# SmartCard.net
KiCad netlist of a schematic drawn in Altium Designer
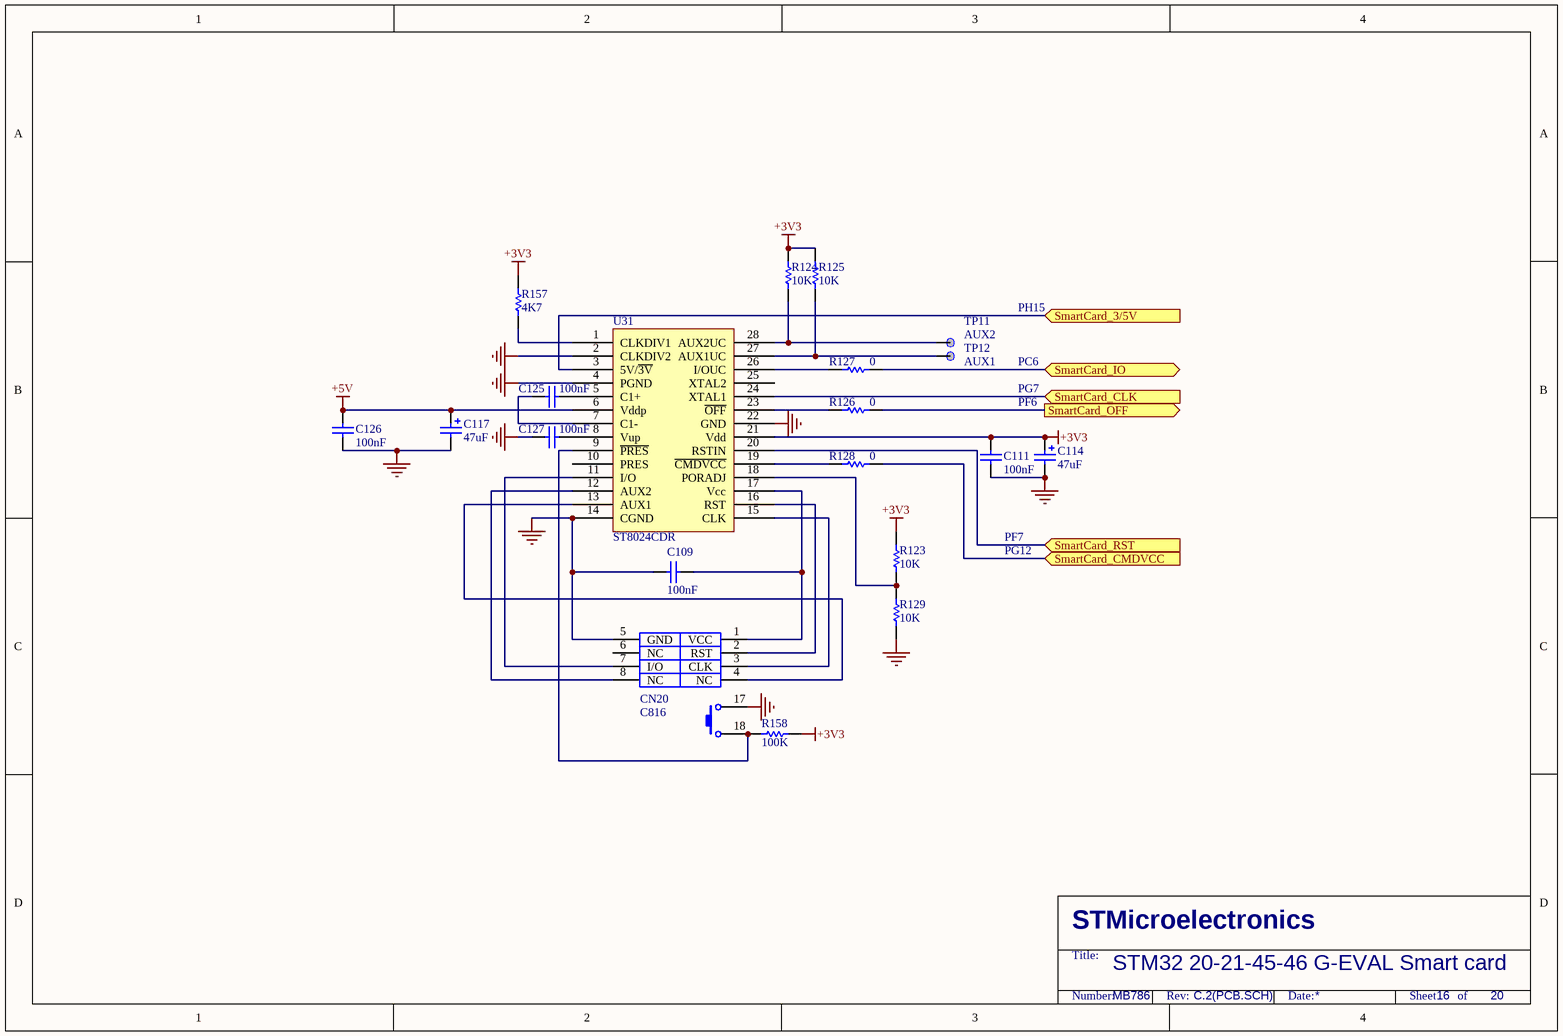
[diagram p0: SmartCard.SchDoc]

(export (version "E")
  (design (tool "Eeschema 10.0.6"))
  (components
    (comp (ref "C109")
      (value "100nF")
      (footprint "0402C")
      (description "Capacitor")
      (fields (field (name "PUBLISHER") "Altium Limited"))
      (libsource (lib "Miscellaneous Devices") (part "CAP"))
    )
    (comp (ref "C111")
      (value "100nF")
      (footprint "0402C")
      (description "Capacitor")
      (fields (field (name "PUBLISHER") "Altium Limited"))
      (libsource (lib "Miscellaneous Devices") (part "CAP"))
    )
    (comp (ref "C114")
      (value "47uF")
      (footprint "TAN-B")
      (description "Polarized Capacitor (Radial)")
      (fields (field (name "PUBLISHER") "Altium Limited"))
      (libsource (lib "Miscellaneous Devices") (part "Cap Pol1"))
    )
    (comp (ref "C117")
      (value "47uF")
      (footprint "TAN-B")
      (description "Polarized Capacitor (Radial)")
      (fields (field (name "PUBLISHER") "Altium Limited"))
      (libsource (lib "Miscellaneous Devices") (part "Cap Pol1"))
    )
    (comp (ref "C125")
      (value "100nF")
      (footprint "0402C")
      (description "Capacitor")
      (fields (field (name "PUBLISHER") "Altium Limited"))
      (libsource (lib "Miscellaneous Devices") (part "CAP"))
    )
    (comp (ref "C126")
      (value "100nF")
      (footprint "0402C")
      (description "Capacitor")
      (fields (field (name "PUBLISHER") "Altium Limited"))
      (libsource (lib "Miscellaneous Devices") (part "CAP"))
    )
    (comp (ref "C127")
      (value "100nF")
      (footprint "0402C")
      (description "Capacitor")
      (fields (field (name "PUBLISHER") "Altium Limited"))
      (libsource (lib "Miscellaneous Devices") (part "CAP"))
    )
    (comp (ref "CN20")
      (value "C816")
      (footprint "SAM(C816)")
      (libsource (lib "MB525") (part "Smart_card_CN"))
    )
    (comp (ref "R123")
      (value "10K")
      (footprint "0402R")
      (description "Resistor")
      (fields (field (name "PUBLISHER") "Altium Limited"))
      (libsource (lib "Miscellaneous Devices") (part "Res1"))
    )
    (comp (ref "R124")
      (value "10K")
      (footprint "0402R")
      (description "Resistor")
      (fields (field (name "PUBLISHER") "Altium Limited"))
      (libsource (lib "Miscellaneous Devices") (part "Res1"))
    )
    (comp (ref "R125")
      (value "10K")
      (footprint "0402R")
      (description "Resistor")
      (fields (field (name "PUBLISHER") "Altium Limited"))
      (libsource (lib "Miscellaneous Devices") (part "Res1"))
    )
    (comp (ref "R126")
      (value "0")
      (footprint "0603R")
      (description "Resistor")
      (fields (field (name "PUBLISHER") "Altium Limited"))
      (libsource (lib "Miscellaneous Devices") (part "Res1"))
    )
    (comp (ref "R127")
      (value "0")
      (footprint "0603R")
      (description "Resistor")
      (fields (field (name "PUBLISHER") "Altium Limited"))
      (libsource (lib "Miscellaneous Devices") (part "Res1"))
    )
    (comp (ref "R128")
      (value "0")
      (footprint "0603R")
      (description "Resistor")
      (fields (field (name "PUBLISHER") "Altium Limited"))
      (libsource (lib "Miscellaneous Devices") (part "Res1"))
    )
    (comp (ref "R129")
      (value "10K")
      (footprint "0402R")
      (description "Resistor")
      (fields (field (name "PUBLISHER") "Altium Limited"))
      (libsource (lib "Miscellaneous Devices") (part "Res1"))
    )
    (comp (ref "R157")
      (value "4K7")
      (footprint "0402R")
      (description "Resistor")
      (fields (field (name "PUBLISHER") "Altium Limited"))
      (libsource (lib "Miscellaneous Devices") (part "Res1"))
    )
    (comp (ref "R158")
      (value "100K")
      (footprint "0402R")
      (description "Resistor")
      (fields (field (name "PUBLISHER") "Altium Limited"))
      (libsource (lib "Miscellaneous Devices") (part "Res1"))
    )
    (comp (ref "TP11") (value "AUX2") (footprint "TP") (libsource (lib "*") (part "TP")))
    (comp (ref "TP12") (value "AUX1") (footprint "TP") (libsource (lib "*") (part "TP")))
    (comp (ref "U31") (value "ST8024CDR") (footprint "SO28") (libsource (lib "MB525") (part "ST8024CTR")))
  )
  (nets
    (net (code "1") (name "+3V3") (class "Default")
      (node (ref "C111") (pin "1") (pinfunction "1_1") (pintype "passive"))
      (node (ref "C114") (pin "1") (pinfunction "1_1") (pintype "passive"))
      (node (ref "R123") (pin "1") (pinfunction "1_1") (pintype "passive"))
      (node (ref "R124") (pin "1") (pinfunction "1_1") (pintype "passive"))
      (node (ref "R125") (pin "1") (pinfunction "1_1") (pintype "passive"))
      (node (ref "R157") (pin "1") (pinfunction "1_1") (pintype "passive"))
      (node (ref "R158") (pin "1") (pinfunction "1_1") (pintype "passive"))
      (node (ref "U31") (pin "21") (pinfunction "Vdd_21") (pintype "passive"))
    )
    (net (code "2") (name "+5V") (class "Default")
      (node (ref "C117") (pin "1") (pinfunction "1_1") (pintype "passive"))
      (node (ref "C126") (pin "1") (pinfunction "1_1") (pintype "passive"))
      (node (ref "U31") (pin "6") (pinfunction "Vddp_6") (pintype "passive"))
    )
    (net (code "3") (name "/SmartCard_3{slash}5V") (class "Default")
      (node (ref "U31") (pin "3") (pinfunction "5V/~{3V}_3") (pintype "passive"))
    )
    (net (code "4") (name "/SmartCard_CLK") (class "Default")
      (node (ref "U31") (pin "24") (pinfunction "XTAL1_24") (pintype "passive"))
    )
    (net (code "5") (name "/SmartCard_CMDVCC") (class "Default")
      (node (ref "R128") (pin "1") (pinfunction "1_1") (pintype "passive"))
    )
    (net (code "6") (name "/SmartCard_IO") (class "Default")
      (node (ref "R127") (pin "2") (pinfunction "2_2") (pintype "passive"))
    )
    (net (code "7") (name "/SmartCard_OFF") (class "Default")
      (node (ref "R126") (pin "1") (pinfunction "1_1") (pintype "passive"))
    )
    (net (code "8") (name "/SmartCard_RST") (class "Default")
      (node (ref "U31") (pin "20") (pinfunction "RSTIN_20") (pintype "passive"))
    )
    (net (code "9") (name "GND") (class "Default")
      (node (ref "C109") (pin "1") (pinfunction "1_1") (pintype "passive"))
      (node (ref "C111") (pin "2") (pinfunction "2_2") (pintype "passive"))
      (node (ref "C114") (pin "2") (pinfunction "2_2") (pintype "passive"))
      (node (ref "C117") (pin "2") (pinfunction "2_2") (pintype "passive"))
      (node (ref "C126") (pin "2") (pinfunction "2_2") (pintype "passive"))
      (node (ref "C127") (pin "2") (pinfunction "2_2") (pintype "passive"))
      (node (ref "CN20") (pin "17") (pintype "passive"))
      (node (ref "CN20") (pin "5") (pinfunction "GND_5") (pintype "passive"))
      (node (ref "R129") (pin "2") (pinfunction "2_2") (pintype "passive"))
      (node (ref "U31") (pin "14") (pinfunction "CGND_14") (pintype "passive"))
      (node (ref "U31") (pin "2") (pinfunction "CLKDIV2_2") (pintype "passive"))
      (node (ref "U31") (pin "22") (pinfunction "GND_22") (pintype "passive"))
      (node (ref "U31") (pin "4") (pinfunction "PGND_4") (pintype "passive"))
    )
    (net (code "10") (name "Net-(CN20-CLK)") (class "Default")
      (node (ref "CN20") (pin "3") (pinfunction "CLK_3") (pintype "passive"))
      (node (ref "U31") (pin "15") (pinfunction "CLK_15") (pintype "passive"))
    )
    (net (code "11") (name "Net-(CN20-I{slash}O)") (class "Default")
      (node (ref "CN20") (pin "7") (pinfunction "I/O_7") (pintype "passive"))
      (node (ref "U31") (pin "11") (pinfunction "I/O_11") (pintype "passive"))
    )
    (net (code "12") (name "Net-(CN20-RST)") (class "Default")
      (node (ref "CN20") (pin "2") (pinfunction "RST_2") (pintype "passive"))
      (node (ref "U31") (pin "16") (pinfunction "RST_16") (pintype "passive"))
    )
    (net (code "13") (name "Net-(CN20-VCC)") (class "Default")
      (node (ref "C109") (pin "2") (pinfunction "2_2") (pintype "passive"))
      (node (ref "CN20") (pin "1") (pinfunction "VCC_1") (pintype "passive"))
      (node (ref "U31") (pin "17") (pinfunction "Vcc_17") (pintype "passive"))
    )
    (net (code "14") (name "Net-(U31-AUX1)") (class "Default")
      (node (ref "CN20") (pin "4") (pinfunction "NC_4") (pintype "passive"))
      (node (ref "U31") (pin "13") (pinfunction "AUX1_13") (pintype "passive"))
    )
    (net (code "15") (name "Net-(U31-AUX1UC)") (class "Default")
      (node (ref "R125") (pin "2") (pinfunction "2_2") (pintype "passive"))
      (node (ref "TP12") (pin "1") (pinfunction "1_1") (pintype "passive"))
      (node (ref "U31") (pin "27") (pinfunction "AUX1UC_27") (pintype "passive"))
    )
    (net (code "16") (name "Net-(U31-AUX2)") (class "Default")
      (node (ref "CN20") (pin "8") (pinfunction "NC_8") (pintype "passive"))
      (node (ref "U31") (pin "12") (pinfunction "AUX2_12") (pintype "passive"))
    )
    (net (code "17") (name "Net-(U31-AUX2UC)") (class "Default")
      (node (ref "R124") (pin "2") (pinfunction "2_2") (pintype "passive"))
      (node (ref "TP11") (pin "1") (pinfunction "1_1") (pintype "passive"))
      (node (ref "U31") (pin "28") (pinfunction "AUX2UC_28") (pintype "passive"))
    )
    (net (code "18") (name "Net-(U31-C1+)") (class "Default")
      (node (ref "C125") (pin "2") (pinfunction "2_2") (pintype "passive"))
      (node (ref "U31") (pin "5") (pinfunction "C1+_5") (pintype "passive"))
    )
    (net (code "19") (name "Net-(U31-C1-)") (class "Default")
      (node (ref "C125") (pin "1") (pinfunction "1_1") (pintype "passive"))
      (node (ref "U31") (pin "7") (pinfunction "C1-_7") (pintype "passive"))
    )
    (net (code "20") (name "Net-(U31-CLKDIV1)") (class "Default")
      (node (ref "R157") (pin "2") (pinfunction "2_2") (pintype "passive"))
      (node (ref "U31") (pin "1") (pinfunction "CLKDIV1_1") (pintype "passive"))
    )
    (net (code "21") (name "Net-(U31-I{slash}OUC)") (class "Default")
      (node (ref "R127") (pin "1") (pinfunction "1_1") (pintype "passive"))
      (node (ref "U31") (pin "26") (pinfunction "I/OUC_26") (pintype "passive"))
    )
    (net (code "22") (name "Net-(U31-PORADJ)") (class "Default")
      (node (ref "R123") (pin "2") (pinfunction "2_2") (pintype "passive"))
      (node (ref "R129") (pin "1") (pinfunction "1_1") (pintype "passive"))
      (node (ref "U31") (pin "18") (pinfunction "PORADJ_18") (pintype "passive"))
    )
    (net (code "23") (name "Net-(U31-Vup)") (class "Default")
      (node (ref "C127") (pin "1") (pinfunction "1_1") (pintype "passive"))
      (node (ref "U31") (pin "8") (pinfunction "Vup_8") (pintype "passive"))
    )
    (net (code "24") (name "Net-(U31-~{CMDVCC})") (class "Default")
      (node (ref "R128") (pin "2") (pinfunction "2_2") (pintype "passive"))
      (node (ref "U31") (pin "19") (pinfunction "~{CMDVCC}_19") (pintype "passive"))
    )
    (net (code "25") (name "Net-(U31-~{OFF})") (class "Default")
      (node (ref "R126") (pin "2") (pinfunction "2_2") (pintype "passive"))
      (node (ref "U31") (pin "23") (pinfunction "~{OFF}_23") (pintype "passive"))
    )
    (net (code "26") (name "Net-(U31-~{PRES})") (class "Default")
      (node (ref "CN20") (pin "18") (pintype "passive"))
      (node (ref "R158") (pin "2") (pinfunction "2_2") (pintype "passive"))
      (node (ref "U31") (pin "9") (pinfunction "~{PRES}_9") (pintype "passive"))
    )
    (net (code "27") (name "unconnected-(CN20-NC-Pad6)") (class "Default")
      (node (ref "CN20") (pin "6") (pinfunction "NC_6") (pintype "passive"))
    )
    (net (code "28") (name "unconnected-(U31-PRES-Pad10)") (class "Default")
      (node (ref "U31") (pin "10") (pinfunction "PRES_10") (pintype "passive"))
    )
    (net (code "29") (name "unconnected-(U31-XTAL2-Pad25)") (class "Default")
      (node (ref "U31") (pin "25") (pinfunction "XTAL2_25") (pintype "passive"))
    )
  )
)
